# Patient_Protection.net
KiCad netlist of a schematic drawn in Altium Designer
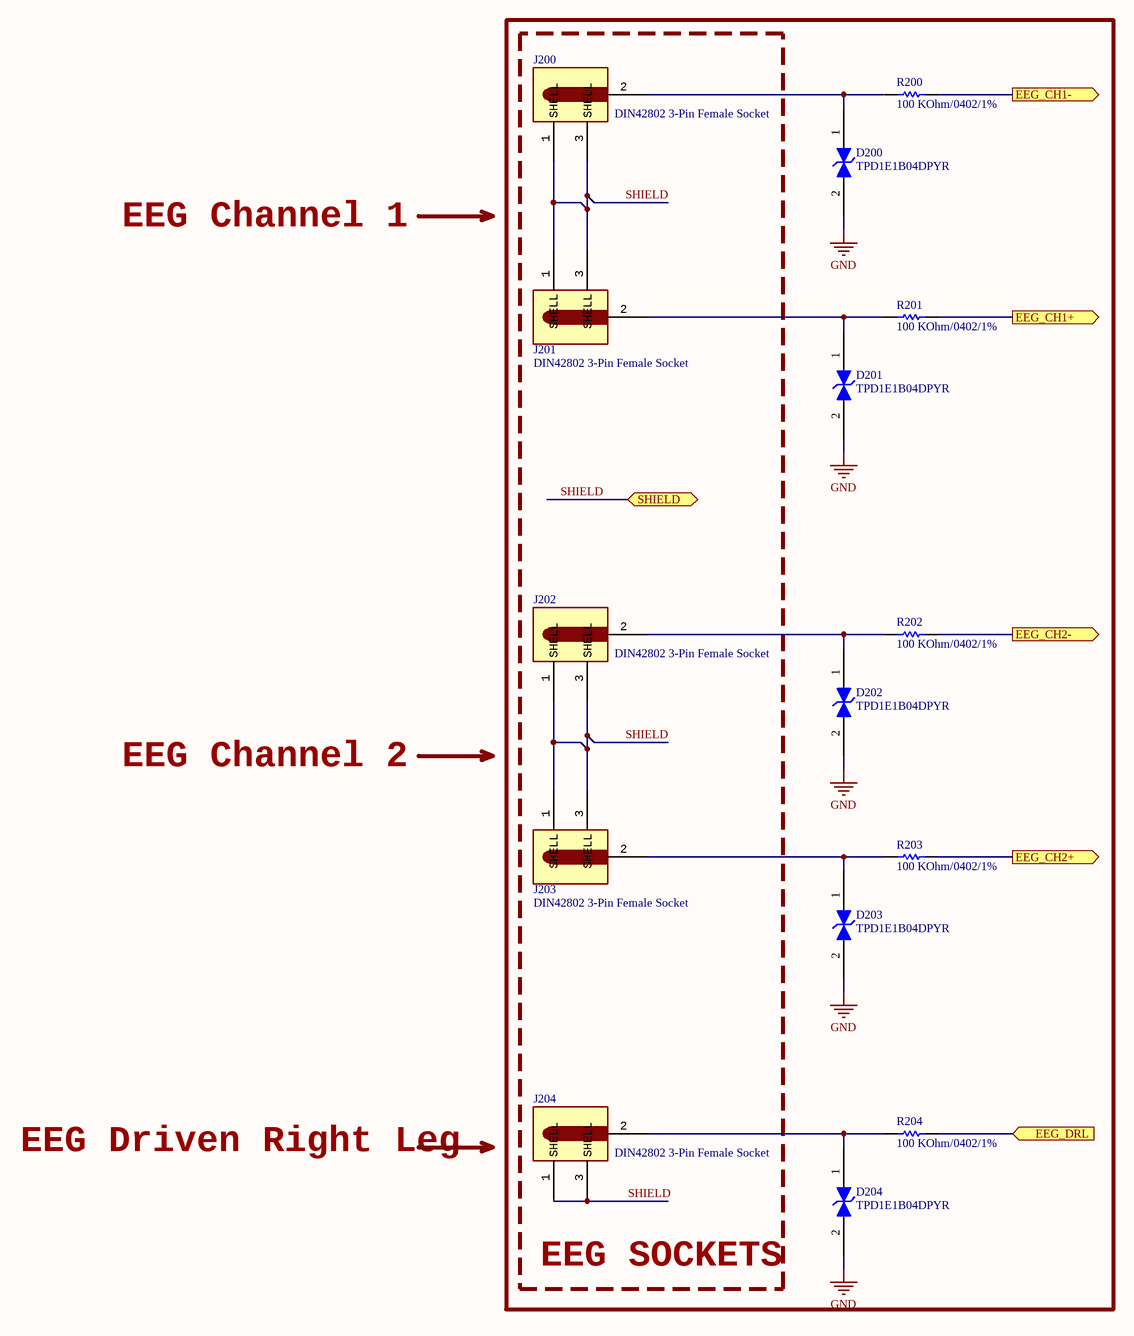
[diagram p0: Patient Protection.SchDoc]

(export (version "E")
  (design (tool "Eeschema 10.0.6"))
  (components
    (comp (ref "D200")
      (value "TPD1E1B04DPYR")
      (footprint "DIO_TPD1E05U06DPYR")
      (description "8.5V (Typ) Clamp 6.3A (8/20µs) Ipp Tvs Diode Surface Mount 2-X1SON (1x.60)")
      (fields (field (name "MF") "Texas Instruments"))
      (libsource (lib "Giang_Diode") (part "TPD1E1B04DPYR"))
    )
    (comp (ref "D201")
      (value "TPD1E1B04DPYR")
      (footprint "DIO_TPD1E05U06DPYR")
      (description "8.5V (Typ) Clamp 6.3A (8/20µs) Ipp Tvs Diode Surface Mount 2-X1SON (1x.60)")
      (fields (field (name "MF") "Texas Instruments"))
      (libsource (lib "Giang_Diode") (part "TPD1E1B04DPYR"))
    )
    (comp (ref "D202")
      (value "TPD1E1B04DPYR")
      (footprint "DIO_TPD1E05U06DPYR")
      (description "8.5V (Typ) Clamp 6.3A (8/20µs) Ipp Tvs Diode Surface Mount 2-X1SON (1x.60)")
      (fields (field (name "MF") "Texas Instruments"))
      (libsource (lib "Giang_Diode") (part "TPD1E1B04DPYR"))
    )
    (comp (ref "D203")
      (value "TPD1E1B04DPYR")
      (footprint "DIO_TPD1E05U06DPYR")
      (description "8.5V (Typ) Clamp 6.3A (8/20µs) Ipp Tvs Diode Surface Mount 2-X1SON (1x.60)")
      (fields (field (name "MF") "Texas Instruments"))
      (libsource (lib "Giang_Diode") (part "TPD1E1B04DPYR"))
    )
    (comp (ref "D204")
      (value "TPD1E1B04DPYR")
      (footprint "DIO_TPD1E05U06DPYR")
      (description "8.5V (Typ) Clamp 6.3A (8/20µs) Ipp Tvs Diode Surface Mount 2-X1SON (1x.60)")
      (fields (field (name "MF") "Texas Instruments"))
      (libsource (lib "Giang_Diode") (part "TPD1E1B04DPYR"))
    )
    (comp (ref "J200")
      (value "DIN42802 3-Pin Female Socket")
      (footprint "DIN42802-1.5MM SOCKET")
      (description "3 PIN Socket Female Socket for PCB EEG EMG DIN42802 1.5 mm Connector")
      (fields (field (name "Comment") "DIN42802 1.5mm"))
      (libsource (lib "Giang's Libs") (part "DIN42802 1.5mm"))
    )
    (comp (ref "J201")
      (value "DIN42802 3-Pin Female Socket")
      (footprint "DIN42802-1.5MM SOCKET")
      (description "3 PIN Socket Female Socket for PCB EEG EMG DIN42802 1.5 mm Connector")
      (fields (field (name "Comment") "DIN42802 1.5mm"))
      (libsource (lib "") (part "DIN42802 1.5mm_1"))
    )
    (comp (ref "J202")
      (value "DIN42802 3-Pin Female Socket")
      (footprint "DIN42802-1.5MM SOCKET")
      (description "3 PIN Socket Female Socket for PCB EEG EMG DIN42802 1.5 mm Connector")
      (fields (field (name "Comment") "DIN42802 1.5mm"))
      (libsource (lib "Giang's Libs") (part "DIN42802 1.5mm"))
    )
    (comp (ref "J203")
      (value "DIN42802 3-Pin Female Socket")
      (footprint "DIN42802-1.5MM SOCKET")
      (description "3 PIN Socket Female Socket for PCB EEG EMG DIN42802 1.5 mm Connector")
      (fields (field (name "Comment") "DIN42802 1.5mm"))
      (libsource (lib "") (part "DIN42802 1.5mm_1"))
    )
    (comp (ref "J204")
      (value "DIN42802 3-Pin Female Socket")
      (footprint "DIN42802-1.5MM SOCKET")
      (description "3 PIN Socket Female Socket for PCB EEG EMG DIN42802 1.5 mm Connector")
      (fields (field (name "Comment") "DIN42802 1.5mm"))
      (libsource (lib "Giang's Libs") (part "DIN42802 1.5mm"))
    )
    (comp (ref "R200")
      (value "100 KOhm/0402/1%")
      (footprint "R0402")
      (description "Code 104, 1/16W 1%")
      (fields (field (name "Comment") "Resistor 100 KOhm 0402 1%"))
      (libsource (lib "Giang_Resistor") (part "Resistor 100 KOhm 0402 1%"))
    )
    (comp (ref "R201")
      (value "100 KOhm/0402/1%")
      (footprint "R0402")
      (description "Code 104, 1/16W 1%")
      (fields (field (name "Comment") "Resistor 100 KOhm 0402 1%"))
      (libsource (lib "Giang_Resistor") (part "Resistor 100 KOhm 0402 1%"))
    )
    (comp (ref "R202")
      (value "100 KOhm/0402/1%")
      (footprint "R0402")
      (description "Code 104, 1/16W 1%")
      (fields (field (name "Comment") "Resistor 100 KOhm 0402 1%"))
      (libsource (lib "Giang_Resistor") (part "Resistor 100 KOhm 0402 1%"))
    )
    (comp (ref "R203")
      (value "100 KOhm/0402/1%")
      (footprint "R0402")
      (description "Code 104, 1/16W 1%")
      (fields (field (name "Comment") "Resistor 100 KOhm 0402 1%"))
      (libsource (lib "Giang_Resistor") (part "Resistor 100 KOhm 0402 1%"))
    )
    (comp (ref "R204")
      (value "100 KOhm/0402/1%")
      (footprint "R0402")
      (description "Code 104, 1/16W 1%")
      (fields (field (name "Comment") "Resistor 100 KOhm 0402 1%"))
      (libsource (lib "Giang_Resistor") (part "Resistor 100 KOhm 0402 1%"))
    )
  )
  (nets
    (net (code "1") (name "/EEG_CH1+") (class "Default")
      (node (ref "R201") (pin "2") (pinfunction "2_2") (pintype "passive"))
    )
    (net (code "2") (name "/EEG_CH1-") (class "Default")
      (node (ref "R200") (pin "2") (pinfunction "2_2") (pintype "passive"))
    )
    (net (code "3") (name "/EEG_CH2+") (class "Default")
      (node (ref "R203") (pin "2") (pinfunction "2_2") (pintype "passive"))
    )
    (net (code "4") (name "/EEG_CH2-") (class "Default")
      (node (ref "R202") (pin "2") (pinfunction "2_2") (pintype "passive"))
    )
    (net (code "5") (name "/EEG_DRL") (class "Default")
      (node (ref "R204") (pin "2") (pinfunction "2_2") (pintype "passive"))
    )
    (net (code "6") (name "/SHIELD") (class "Default")
      (node (ref "J200") (pin "1") (pinfunction "SHELL_1") (pintype "passive"))
      (node (ref "J200") (pin "3") (pinfunction "SHELL_3") (pintype "passive"))
      (node (ref "J201") (pin "1") (pinfunction "SHELL_1") (pintype "passive"))
      (node (ref "J201") (pin "3") (pinfunction "SHELL_3") (pintype "passive"))
      (node (ref "J202") (pin "1") (pinfunction "SHELL_1") (pintype "passive"))
      (node (ref "J202") (pin "3") (pinfunction "SHELL_3") (pintype "passive"))
      (node (ref "J203") (pin "1") (pinfunction "SHELL_1") (pintype "passive"))
      (node (ref "J203") (pin "3") (pinfunction "SHELL_3") (pintype "passive"))
      (node (ref "J204") (pin "1") (pinfunction "SHELL_1") (pintype "passive"))
      (node (ref "J204") (pin "3") (pinfunction "SHELL_3") (pintype "passive"))
    )
    (net (code "7") (name "GND") (class "Default")
      (node (ref "D200") (pin "2") (pinfunction "4_2") (pintype "passive"))
      (node (ref "D201") (pin "2") (pinfunction "4_2") (pintype "passive"))
      (node (ref "D202") (pin "2") (pinfunction "4_2") (pintype "passive"))
      (node (ref "D203") (pin "2") (pinfunction "4_2") (pintype "passive"))
      (node (ref "D204") (pin "2") (pinfunction "4_2") (pintype "passive"))
    )
    (net (code "8") (name "Net-(D200-3)") (class "Default")
      (node (ref "D200") (pin "1") (pinfunction "3_1") (pintype "passive"))
      (node (ref "J200") (pin "2") (pinfunction "PORT_2") (pintype "passive"))
      (node (ref "R200") (pin "1") (pinfunction "1_1") (pintype "passive"))
    )
    (net (code "9") (name "Net-(D201-3)") (class "Default")
      (node (ref "D201") (pin "1") (pinfunction "3_1") (pintype "passive"))
      (node (ref "J201") (pin "2") (pinfunction "PORT_2") (pintype "passive"))
      (node (ref "R201") (pin "1") (pinfunction "1_1") (pintype "passive"))
    )
    (net (code "10") (name "Net-(D202-3)") (class "Default")
      (node (ref "D202") (pin "1") (pinfunction "3_1") (pintype "passive"))
      (node (ref "J202") (pin "2") (pinfunction "PORT_2") (pintype "passive"))
      (node (ref "R202") (pin "1") (pinfunction "1_1") (pintype "passive"))
    )
    (net (code "11") (name "Net-(D203-3)") (class "Default")
      (node (ref "D203") (pin "1") (pinfunction "3_1") (pintype "passive"))
      (node (ref "J203") (pin "2") (pinfunction "PORT_2") (pintype "passive"))
      (node (ref "R203") (pin "1") (pinfunction "1_1") (pintype "passive"))
    )
    (net (code "12") (name "Net-(D204-3)") (class "Default")
      (node (ref "D204") (pin "1") (pinfunction "3_1") (pintype "passive"))
      (node (ref "J204") (pin "2") (pinfunction "PORT_2") (pintype "passive"))
      (node (ref "R204") (pin "1") (pinfunction "1_1") (pintype "passive"))
    )
  )
)
